# stepper_motor_control_sch.net
KiCad netlist of a schematic drawn in Altium Designer
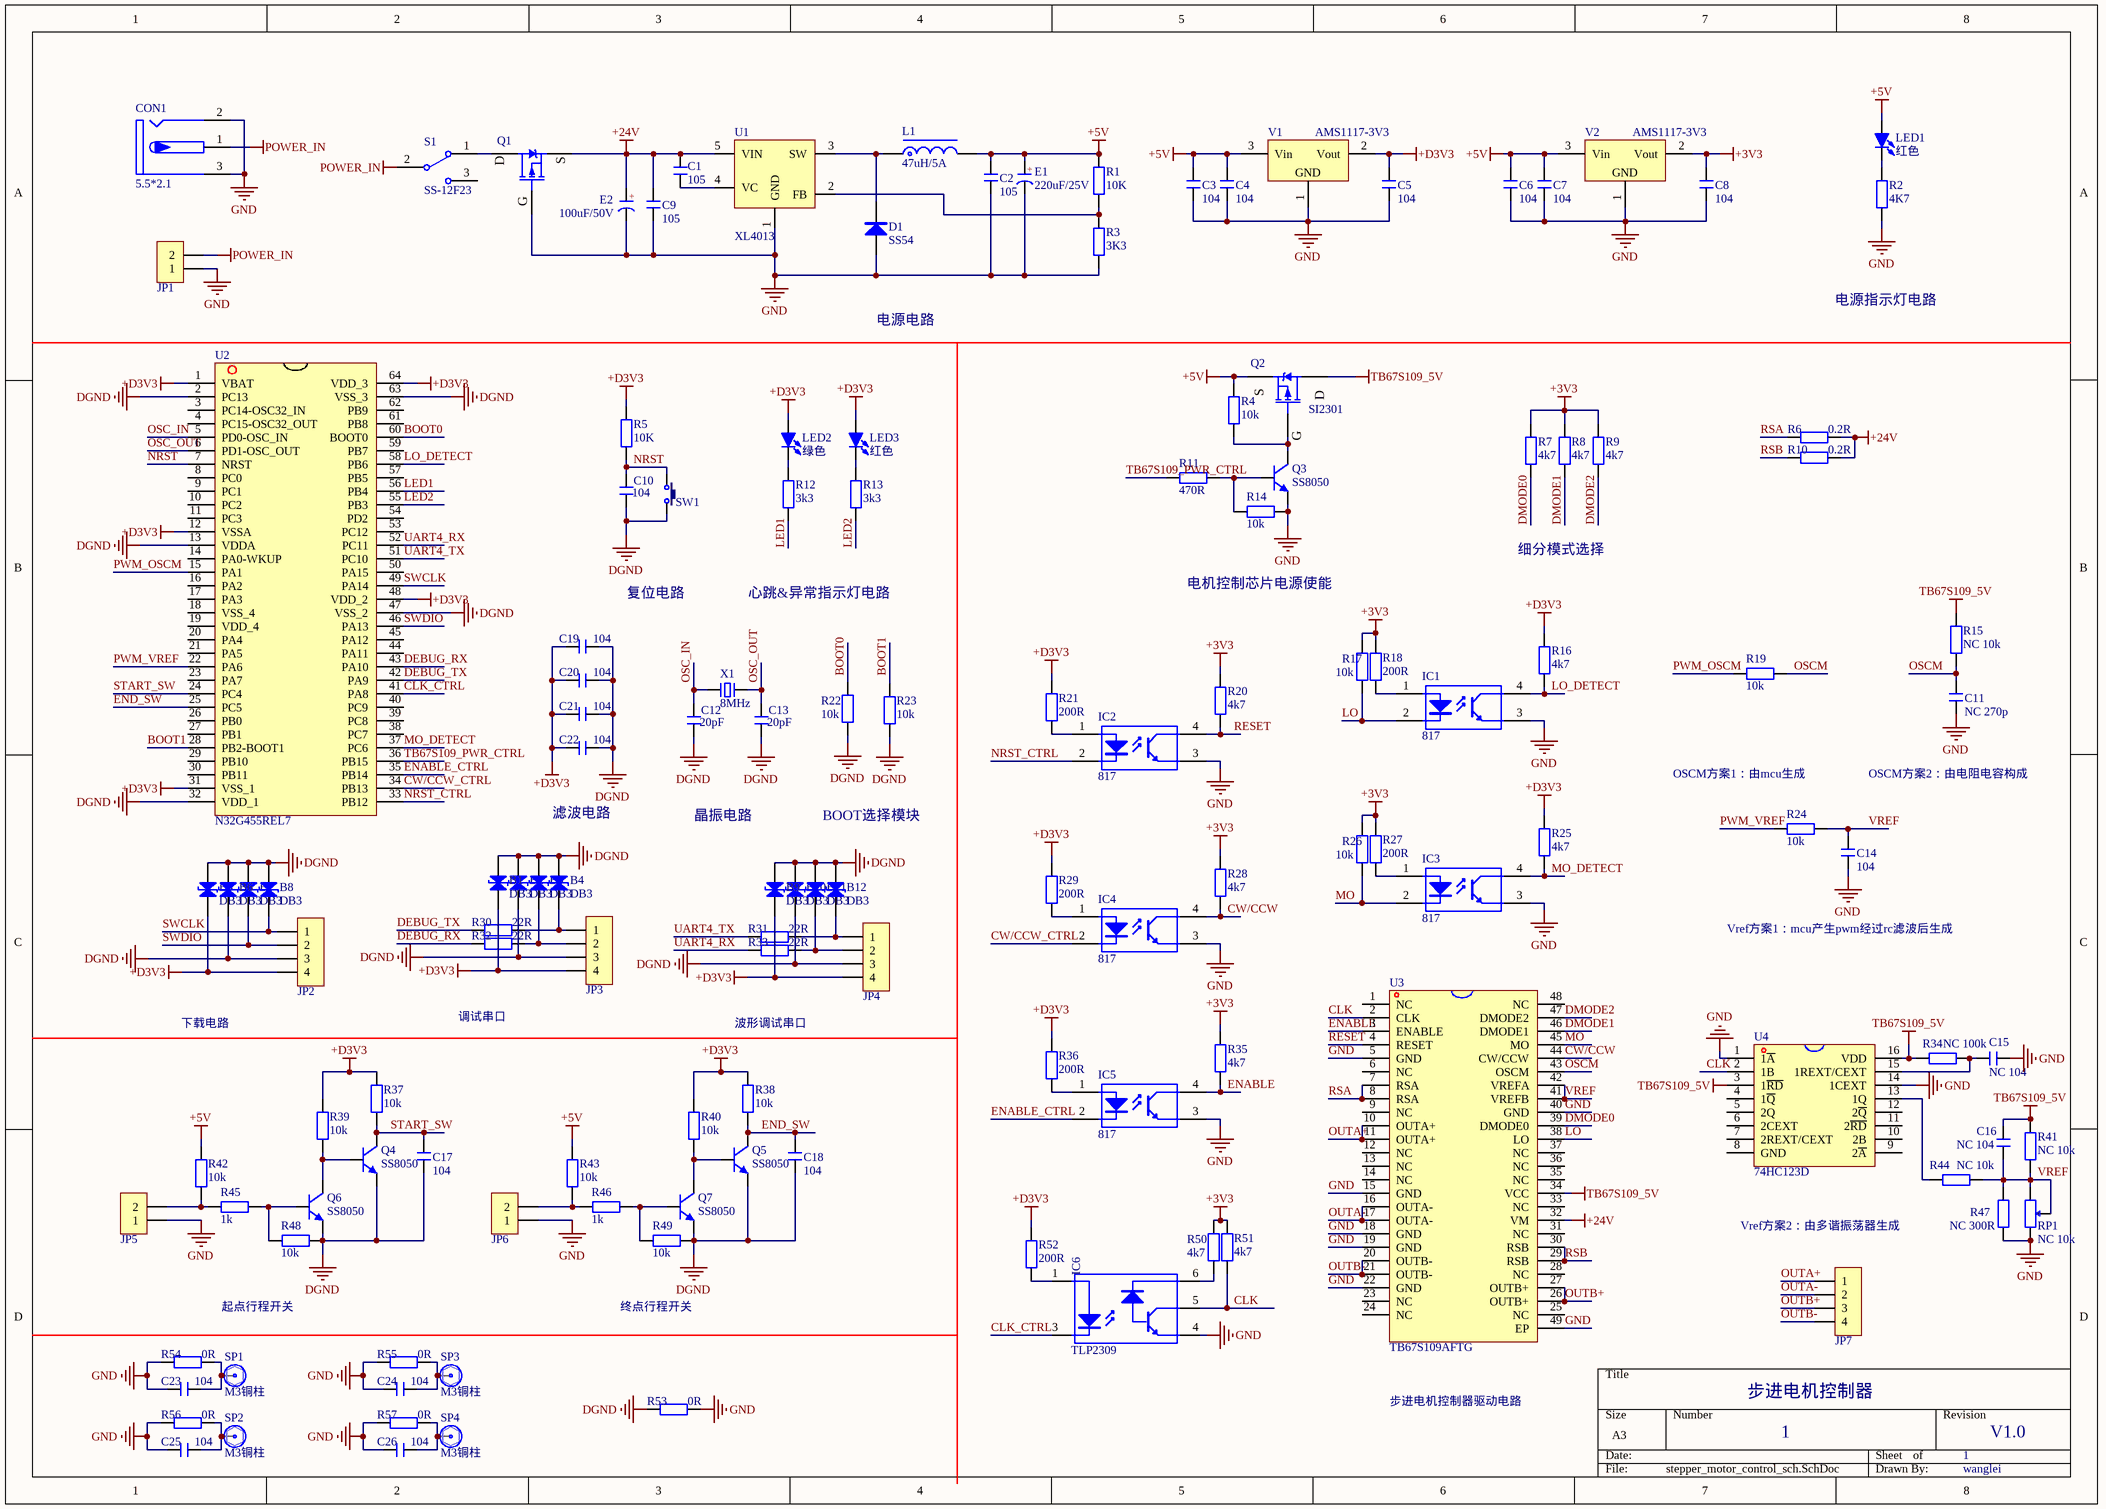
[diagram p0: stepper_motor_control_sch.SchDoc]

(export (version "E")
  (design (tool "Eeschema 10.0.6"))
  (components
    (comp (ref "B1")
      (value "DB3")
      (footprint "SOD-323")
      (description "双向触发二极管")
      (libsource (lib "8.1   - 二极管-整流桥") (part "DB3"))
    )
    (comp (ref "B2")
      (value "DB3")
      (footprint "SOD-323")
      (description "双向触发二极管")
      (libsource (lib "8.1   - 二极管-整流桥") (part "DB3"))
    )
    (comp (ref "B3")
      (value "DB3")
      (footprint "SOD-323")
      (description "双向触发二极管")
      (libsource (lib "8.1   - 二极管-整流桥") (part "DB3"))
    )
    (comp (ref "B4")
      (value "DB3")
      (footprint "SOD-323")
      (description "双向触发二极管")
      (libsource (lib "8.1   - 二极管-整流桥") (part "DB3"))
    )
    (comp (ref "B5")
      (value "DB3")
      (footprint "SOD-323")
      (description "双向触发二极管")
      (libsource (lib "8.1   - 二极管-整流桥") (part "DB3"))
    )
    (comp (ref "B6")
      (value "DB3")
      (footprint "SOD-323")
      (description "双向触发二极管")
      (libsource (lib "8.1   - 二极管-整流桥") (part "DB3"))
    )
    (comp (ref "B7")
      (value "DB3")
      (footprint "SOD-323")
      (description "双向触发二极管")
      (libsource (lib "8.1   - 二极管-整流桥") (part "DB3"))
    )
    (comp (ref "B8")
      (value "DB3")
      (footprint "SOD-323")
      (description "双向触发二极管")
      (libsource (lib "8.1   - 二极管-整流桥") (part "DB3"))
    )
    (comp (ref "B9")
      (value "DB3")
      (footprint "SOD-323")
      (description "双向触发二极管")
      (libsource (lib "8.1   - 二极管-整流桥") (part "DB3"))
    )
    (comp (ref "B10")
      (value "DB3")
      (footprint "SOD-323")
      (description "双向触发二极管")
      (libsource (lib "8.1   - 二极管-整流桥") (part "DB3"))
    )
    (comp (ref "B11")
      (value "DB3")
      (footprint "SOD-323")
      (description "双向触发二极管")
      (libsource (lib "8.1   - 二极管-整流桥") (part "DB3"))
    )
    (comp (ref "B12")
      (value "DB3")
      (footprint "SOD-323")
      (description "双向触发二极管")
      (libsource (lib "8.1   - 二极管-整流桥") (part "DB3"))
    )
    (comp (ref "C1")
      (value "105")
      (footprint "C 0603_M")
      (description "无极性贴片电容")
      (fields (field (name "版权归属") "源创客"))
      (libsource (lib "3.1   - 电阻-电容-电感") (part "C"))
    )
    (comp (ref "C2")
      (value "105")
      (footprint "C 0603_M")
      (description "无极性贴片电容")
      (fields (field (name "版权归属") "源创客"))
      (libsource (lib "3.1   - 电阻-电容-电感") (part "C"))
    )
    (comp (ref "C3")
      (value "104")
      (footprint "C 0603_M")
      (description "无极性贴片电容")
      (fields (field (name "版权归属") "源创客"))
      (libsource (lib "3.1   - 电阻-电容-电感") (part "C"))
    )
    (comp (ref "C4")
      (value "104")
      (footprint "C 0603_M")
      (description "无极性贴片电容")
      (fields (field (name "版权归属") "源创客"))
      (libsource (lib "3.1   - 电阻-电容-电感") (part "C"))
    )
    (comp (ref "C5")
      (value "104")
      (footprint "C 0603_M")
      (description "无极性贴片电容")
      (fields (field (name "版权归属") "源创客"))
      (libsource (lib "3.1   - 电阻-电容-电感") (part "C"))
    )
    (comp (ref "C6")
      (value "104")
      (footprint "C 0603_M")
      (description "无极性贴片电容")
      (fields (field (name "版权归属") "源创客"))
      (libsource (lib "3.1   - 电阻-电容-电感") (part "C"))
    )
    (comp (ref "C7")
      (value "104")
      (footprint "C 0603_M")
      (description "无极性贴片电容")
      (fields (field (name "版权归属") "源创客"))
      (libsource (lib "3.1   - 电阻-电容-电感") (part "C"))
    )
    (comp (ref "C8")
      (value "104")
      (footprint "C 0603_M")
      (description "无极性贴片电容")
      (fields (field (name "版权归属") "源创客"))
      (libsource (lib "3.1   - 电阻-电容-电感") (part "C"))
    )
    (comp (ref "C9")
      (value "105")
      (footprint "C 0603_M")
      (description "无极性贴片电容")
      (fields (field (name "版权归属") "源创客"))
      (libsource (lib "3.1   - 电阻-电容-电感") (part "C"))
    )
    (comp (ref "C10")
      (value "104")
      (footprint "C 0603_M")
      (description "无极性贴片电容")
      (fields (field (name "版权归属") "源创客"))
      (libsource (lib "3.1   - 电阻-电容-电感") (part "C"))
    )
    (comp (ref "C11")
      (value "NC 270p")
      (footprint "C 0603_M")
      (description "无极性贴片电容")
      (fields (field (name "版权归属") "源创客"))
      (libsource (lib "3.1   - 电阻-电容-电感") (part "C"))
    )
    (comp (ref "C12")
      (value "20pF")
      (footprint "C 0603_M")
      (description "无极性贴片电容")
      (fields (field (name "版权归属") "源创客"))
      (libsource (lib "3.1   - 电阻-电容-电感") (part "C"))
    )
    (comp (ref "C13")
      (value "20pF")
      (footprint "C 0603_M")
      (description "无极性贴片电容")
      (fields (field (name "版权归属") "源创客"))
      (libsource (lib "3.1   - 电阻-电容-电感") (part "C"))
    )
    (comp (ref "C14")
      (value "104")
      (footprint "C 0603_M")
      (description "无极性贴片电容")
      (fields (field (name "版权归属") "源创客"))
      (libsource (lib "3.1   - 电阻-电容-电感") (part "C"))
    )
    (comp (ref "C15")
      (value "NC 104")
      (footprint "C 0603_M")
      (description "无极性贴片电容")
      (fields (field (name "版权归属") "源创客"))
      (libsource (lib "3.1   - 电阻-电容-电感") (part "C"))
    )
    (comp (ref "C16")
      (value "NC 104")
      (footprint "C 0603_M")
      (description "无极性贴片电容")
      (fields (field (name "版权归属") "源创客"))
      (libsource (lib "3.1   - 电阻-电容-电感") (part "C"))
    )
    (comp (ref "C17")
      (value "104")
      (footprint "C 0603_M")
      (description "无极性贴片电容")
      (fields (field (name "版权归属") "源创客"))
      (libsource (lib "3.1   - 电阻-电容-电感") (part "C"))
    )
    (comp (ref "C18")
      (value "104")
      (footprint "C 0603_M")
      (description "无极性贴片电容")
      (fields (field (name "版权归属") "源创客"))
      (libsource (lib "3.1   - 电阻-电容-电感") (part "C"))
    )
    (comp (ref "C19")
      (value "104")
      (footprint "C 0603_M")
      (description "无极性贴片电容")
      (fields (field (name "版权归属") "源创客"))
      (libsource (lib "3.1   - 电阻-电容-电感") (part "C"))
    )
    (comp (ref "C20")
      (value "104")
      (footprint "C 0603_M")
      (description "无极性贴片电容")
      (fields (field (name "版权归属") "源创客"))
      (libsource (lib "3.1   - 电阻-电容-电感") (part "C"))
    )
    (comp (ref "C21")
      (value "104")
      (footprint "C 0603_M")
      (description "无极性贴片电容")
      (fields (field (name "版权归属") "源创客"))
      (libsource (lib "3.1   - 电阻-电容-电感") (part "C"))
    )
    (comp (ref "C22")
      (value "104")
      (footprint "C 0603_M")
      (description "无极性贴片电容")
      (fields (field (name "版权归属") "源创客"))
      (libsource (lib "3.1   - 电阻-电容-电感") (part "C"))
    )
    (comp (ref "C23")
      (value "104")
      (footprint "C 0603_M")
      (description "无极性贴片电容")
      (fields (field (name "版权归属") "源创客"))
      (libsource (lib "3.1   - 电阻-电容-电感") (part "C"))
    )
    (comp (ref "C24")
      (value "104")
      (footprint "C 0603_M")
      (description "无极性贴片电容")
      (fields (field (name "版权归属") "源创客"))
      (libsource (lib "3.1   - 电阻-电容-电感") (part "C"))
    )
    (comp (ref "C25")
      (value "104")
      (footprint "C 0603_M")
      (description "无极性贴片电容")
      (fields (field (name "版权归属") "源创客"))
      (libsource (lib "3.1   - 电阻-电容-电感") (part "C"))
    )
    (comp (ref "C26")
      (value "104")
      (footprint "C 0603_M")
      (description "无极性贴片电容")
      (fields (field (name "版权归属") "源创客"))
      (libsource (lib "3.1   - 电阻-电容-电感") (part "C"))
    )
    (comp (ref "CON1")
      (value "5.5*2.1")
      (footprint "DC-005")
      (description "带屏蔽DC电源接口")
      (fields (field (name "版权归属") "源创客"))
      (libsource (lib "4.1   - 接口类") (part "DC-005P"))
    )
    (comp (ref "D1")
      (value "SS54")
      (footprint "SMB")
      (description "肖特基二极管")
      (fields (field (name "版权归属") "源创客"))
      (libsource (lib "8.1   - 二极管-整流桥") (part "SS24"))
    )
    (comp (ref "E1")
      (value "220uF/25V")
      (footprint "CAP 2.5*6.3*11.2 - BK")
      (description "直插电解电容")
      (fields (field (name "版权归属") "源创客"))
      (libsource (lib "3.1   - 电阻-电容-电感") (part "C-CAP"))
    )
    (comp (ref "E2")
      (value "100uF/50V")
      (footprint "CAP 3.5*8*11.5 - BK")
      (description "直插电解电容")
      (fields (field (name "版权归属") "源创客"))
      (libsource (lib "3.1   - 电阻-电容-电感") (part "C-CAP"))
    )
    (comp (ref "IC1")
      (value "817")
      (footprint "SMD")
      (description "线性光耦")
      (fields (field (name "版权归属") "源创客"))
      (libsource (lib "11.1 - 传感元件") (part "817"))
    )
    (comp (ref "IC2")
      (value "817")
      (footprint "SMD")
      (description "线性光耦")
      (fields (field (name "版权归属") "源创客"))
      (libsource (lib "11.1 - 传感元件") (part "817"))
    )
    (comp (ref "IC3")
      (value "817")
      (footprint "SMD")
      (description "线性光耦")
      (fields (field (name "版权归属") "源创客"))
      (libsource (lib "11.1 - 传感元件") (part "817"))
    )
    (comp (ref "IC4")
      (value "817")
      (footprint "SMD")
      (description "线性光耦")
      (fields (field (name "版权归属") "源创客"))
      (libsource (lib "11.1 - 传感元件") (part "817"))
    )
    (comp (ref "IC5")
      (value "817")
      (footprint "SMD")
      (description "线性光耦")
      (fields (field (name "版权归属") "源创客"))
      (libsource (lib "11.1 - 传感元件") (part "817"))
    )
    (comp (ref "IC6")
      (value "TLP2309")
      (footprint "SO-6")
      (description "高速光耦")
      (libsource (lib "11.1 - 传感元件") (part "TLP2309"))
    )
    (comp (ref "JP1")
      (value "HDR-1X2")
      (footprint "KF350-2P")
      (description "2P接插件")
      (fields (field (name "版权归属") "源创客"))
      (libsource (lib "4.6   - 接插件-脚距3.5") (part "Header 2"))
    )
    (comp (ref "JP2")
      (value "HDR-1X4")
      (footprint "MX 1.25-WS-4P")
      (description "4P接插件")
      (fields (field (name "版权归属") "源创客"))
      (libsource (lib "4.2   - 接插件-脚距1.25") (part "Header 4"))
    )
    (comp (ref "JP3")
      (value "HDR-1X4")
      (footprint "MX 1.25-WS-4P")
      (description "4P接插件")
      (fields (field (name "版权归属") "源创客"))
      (libsource (lib "4.2   - 接插件-脚距1.25") (part "Header 4"))
    )
    (comp (ref "JP4")
      (value "HDR-1X4")
      (footprint "MX 1.25-WS-4P")
      (description "4P接插件")
      (fields (field (name "版权归属") "源创客"))
      (libsource (lib "4.2   - 接插件-脚距1.25") (part "Header 4"))
    )
    (comp (ref "JP5")
      (value "HDR-1X2")
      (footprint "XH2.54-LI-2P")
      (description "2P接插件")
      (fields (field (name "版权归属") "源创客"))
      (libsource (lib "4.5   - 接插件-脚距2.54") (part "Header 2"))
    )
    (comp (ref "JP6")
      (value "HDR-1X2")
      (footprint "XH2.54-LI-2P")
      (description "2P接插件")
      (fields (field (name "版权归属") "源创客"))
      (libsource (lib "4.5   - 接插件-脚距2.54") (part "Header 2"))
    )
    (comp (ref "JP7")
      (value "HDR-1X4")
      (footprint "KF350-4P")
      (description "4P接插件")
      (fields (field (name "版权归属") "源创客"))
      (libsource (lib "4.6   - 接插件-脚距3.5") (part "Header 4"))
    )
    (comp (ref "L1")
      (value "47uH/5A")
      (footprint "LMR135")
      (description "功率磁环电感")
      (fields (field (name "版权归属") "源创客"))
      (libsource (lib "3.1   - 电阻-电容-电感") (part "L-MR"))
    )
    (comp (ref "LED1")
      (value "红色")
      (footprint "LED 0805W")
      (description "贴片LED")
      (fields (field (name "版权归属") "源创客"))
      (libsource (lib "9.1   - LED") (part "LED-SMD"))
    )
    (comp (ref "LED2")
      (value "绿色")
      (footprint "LED 0805W")
      (description "贴片LED")
      (fields (field (name "版权归属") "源创客"))
      (libsource (lib "9.1   - LED") (part "LED-SMD"))
    )
    (comp (ref "LED3")
      (value "红色")
      (footprint "LED 0805W")
      (description "贴片LED")
      (fields (field (name "版权归属") "源创客"))
      (libsource (lib "9.1   - LED") (part "LED-SMD"))
    )
    (comp (ref "Q1")
      (value "D15P05")
      (footprint "TO252")
      (description "P沟道场效应管")
      (fields (field (name "版权归属") "源创客"))
      (libsource (lib "6.1   - 场效应管-可控硅") (part "D15P05"))
    )
    (comp (ref "Q2")
      (value "SI2301")
      (footprint "SOT23-3N")
      (description "P沟道场效应管")
      (fields (field (name "版权归属") "源创客"))
      (libsource (lib "6.1   - 场效应管-可控硅") (part "SI2301"))
    )
    (comp (ref "Q3")
      (value "SS8050")
      (footprint "SOT23-3N")
      (description "高频放大-NPN型")
      (fields (field (name "版权归属") "源创客"))
      (libsource (lib "6.2   - 三极管") (part "8050-SMD"))
    )
    (comp (ref "Q4")
      (value "SS8050")
      (footprint "SOT23-3N")
      (description "高频放大-NPN型")
      (fields (field (name "版权归属") "源创客"))
      (libsource (lib "6.2   - 三极管") (part "8050-SMD"))
    )
    (comp (ref "Q5")
      (value "SS8050")
      (footprint "SOT23-3N")
      (description "高频放大-NPN型")
      (fields (field (name "版权归属") "源创客"))
      (libsource (lib "6.2   - 三极管") (part "8050-SMD"))
    )
    (comp (ref "Q6")
      (value "SS8050")
      (footprint "SOT23-3N")
      (description "高频放大-NPN型")
      (fields (field (name "版权归属") "源创客"))
      (libsource (lib "6.2   - 三极管") (part "8050-SMD"))
    )
    (comp (ref "Q7")
      (value "SS8050")
      (footprint "SOT23-3N")
      (description "高频放大-NPN型")
      (fields (field (name "版权归属") "源创客"))
      (libsource (lib "6.2   - 三极管") (part "8050-SMD"))
    )
    (comp (ref "R1")
      (value "10K")
      (footprint "R 0603_M")
      (description "贴片电阻")
      (fields (field (name "版权归属") "源创客"))
      (libsource (lib "3.1   - 电阻-电容-电感") (part "R"))
    )
    (comp (ref "R2")
      (value "4K7")
      (footprint "R 0603_M")
      (description "贴片电阻")
      (fields (field (name "版权归属") "源创客"))
      (libsource (lib "3.1   - 电阻-电容-电感") (part "R"))
    )
    (comp (ref "R3")
      (value "3K3")
      (footprint "R 0603_M")
      (description "贴片电阻")
      (fields (field (name "版权归属") "源创客"))
      (libsource (lib "3.1   - 电阻-电容-电感") (part "R"))
    )
    (comp (ref "R4")
      (value "10k")
      (footprint "R 0603_M")
      (description "贴片电阻")
      (fields (field (name "版权归属") "源创客"))
      (libsource (lib "3.1   - 电阻-电容-电感") (part "R"))
    )
    (comp (ref "R5")
      (value "10K")
      (footprint "R 0603_M")
      (description "贴片电阻")
      (fields (field (name "版权归属") "源创客"))
      (libsource (lib "3.1   - 电阻-电容-电感") (part "R"))
    )
    (comp (ref "R6")
      (value "0.2R")
      (footprint "R 2010_M")
      (description "贴片电阻")
      (fields (field (name "版权归属") "源创客"))
      (libsource (lib "3.1   - 电阻-电容-电感") (part "R"))
    )
    (comp (ref "R7")
      (value "4k7")
      (footprint "R 0603_M")
      (description "贴片电阻")
      (fields (field (name "版权归属") "源创客"))
      (libsource (lib "3.1   - 电阻-电容-电感") (part "R"))
    )
    (comp (ref "R8")
      (value "4k7")
      (footprint "R 0603_M")
      (description "贴片电阻")
      (fields (field (name "版权归属") "源创客"))
      (libsource (lib "3.1   - 电阻-电容-电感") (part "R"))
    )
    (comp (ref "R9")
      (value "4k7")
      (footprint "R 0603_M")
      (description "贴片电阻")
      (fields (field (name "版权归属") "源创客"))
      (libsource (lib "3.1   - 电阻-电容-电感") (part "R"))
    )
    (comp (ref "R10")
      (value "0.2R")
      (footprint "R 2010_M")
      (description "贴片电阻")
      (fields (field (name "版权归属") "源创客"))
      (libsource (lib "3.1   - 电阻-电容-电感") (part "R"))
    )
    (comp (ref "R11")
      (value "470R")
      (footprint "R 0603_M")
      (description "贴片电阻")
      (fields (field (name "版权归属") "源创客"))
      (libsource (lib "3.1   - 电阻-电容-电感") (part "R"))
    )
    (comp (ref "R12")
      (value "3k3")
      (footprint "R 0603_M")
      (description "贴片电阻")
      (fields (field (name "版权归属") "源创客"))
      (libsource (lib "3.1   - 电阻-电容-电感") (part "R"))
    )
    (comp (ref "R13")
      (value "3k3")
      (footprint "R 0603_M")
      (description "贴片电阻")
      (fields (field (name "版权归属") "源创客"))
      (libsource (lib "3.1   - 电阻-电容-电感") (part "R"))
    )
    (comp (ref "R14")
      (value "10k")
      (footprint "R 0603_M")
      (description "贴片电阻")
      (fields (field (name "版权归属") "源创客"))
      (libsource (lib "3.1   - 电阻-电容-电感") (part "R"))
    )
    (comp (ref "R15")
      (value "NC 10k")
      (footprint "R 0603_M")
      (description "贴片电阻")
      (fields (field (name "版权归属") "源创客"))
      (libsource (lib "3.1   - 电阻-电容-电感") (part "R"))
    )
    (comp (ref "R16")
      (value "4k7")
      (footprint "R 0603_M")
      (description "贴片电阻")
      (fields (field (name "版权归属") "源创客"))
      (libsource (lib "3.1   - 电阻-电容-电感") (part "R"))
    )
    (comp (ref "R17")
      (value "10k")
      (footprint "R 0603_M")
      (description "贴片电阻")
      (fields (field (name "版权归属") "源创客"))
      (libsource (lib "3.1   - 电阻-电容-电感") (part "R"))
    )
    (comp (ref "R18")
      (value "200R")
      (footprint "R 0603_M")
      (description "贴片电阻")
      (fields (field (name "版权归属") "源创客"))
      (libsource (lib "3.1   - 电阻-电容-电感") (part "R"))
    )
    (comp (ref "R19")
      (value "10k")
      (footprint "R 0603_M")
      (description "贴片电阻")
      (fields (field (name "版权归属") "源创客"))
      (libsource (lib "3.1   - 电阻-电容-电感") (part "R"))
    )
    (comp (ref "R20")
      (value "4k7")
      (footprint "R 0603_M")
      (description "贴片电阻")
      (fields (field (name "版权归属") "源创客"))
      (libsource (lib "3.1   - 电阻-电容-电感") (part "R"))
    )
    (comp (ref "R21")
      (value "200R")
      (footprint "R 0603_M")
      (description "贴片电阻")
      (fields (field (name "版权归属") "源创客"))
      (libsource (lib "3.1   - 电阻-电容-电感") (part "R"))
    )
    (comp (ref "R22")
      (value "10k")
      (footprint "R 0603_M")
      (description "贴片电阻")
      (fields (field (name "版权归属") "源创客"))
      (libsource (lib "3.1   - 电阻-电容-电感") (part "R"))
    )
    (comp (ref "R23")
      (value "10k")
      (footprint "R 0603_M")
      (description "贴片电阻")
      (fields (field (name "版权归属") "源创客"))
      (libsource (lib "3.1   - 电阻-电容-电感") (part "R"))
    )
    (comp (ref "R24")
      (value "10k")
      (footprint "R 0603_M")
      (description "贴片电阻")
      (fields (field (name "版权归属") "源创客"))
      (libsource (lib "3.1   - 电阻-电容-电感") (part "R"))
    )
    (comp (ref "R25")
      (value "4k7")
      (footprint "R 0603_M")
      (description "贴片电阻")
      (fields (field (name "版权归属") "源创客"))
      (libsource (lib "3.1   - 电阻-电容-电感") (part "R"))
    )
    (comp (ref "R26")
      (value "10k")
      (footprint "R 0603_M")
      (description "贴片电阻")
      (fields (field (name "版权归属") "源创客"))
      (libsource (lib "3.1   - 电阻-电容-电感") (part "R"))
    )
    (comp (ref "R27")
      (value "200R")
      (footprint "R 0603_M")
      (description "贴片电阻")
      (fields (field (name "版权归属") "源创客"))
      (libsource (lib "3.1   - 电阻-电容-电感") (part "R"))
    )
    (comp (ref "R28")
      (value "4k7")
      (footprint "R 0603_M")
      (description "贴片电阻")
      (fields (field (name "版权归属") "源创客"))
      (libsource (lib "3.1   - 电阻-电容-电感") (part "R"))
    )
    (comp (ref "R29")
      (value "200R")
      (footprint "R 0603_M")
      (description "贴片电阻")
      (fields (field (name "版权归属") "源创客"))
      (libsource (lib "3.1   - 电阻-电容-电感") (part "R"))
    )
    (comp (ref "R30")
      (value "22R")
      (footprint "R 0603_M")
      (description "贴片电阻")
      (fields (field (name "版权归属") "源创客"))
      (libsource (lib "3.1   - 电阻-电容-电感") (part "R"))
    )
    (comp (ref "R31")
      (value "22R")
      (footprint "R 0603_M")
      (description "贴片电阻")
      (fields (field (name "版权归属") "源创客"))
      (libsource (lib "3.1   - 电阻-电容-电感") (part "R"))
    )
    (comp (ref "R32")
      (value "22R")
      (footprint "R 0603_M")
      (description "贴片电阻")
      (fields (field (name "版权归属") "源创客"))
      (libsource (lib "3.1   - 电阻-电容-电感") (part "R"))
    )
    (comp (ref "R33")
      (value "22R")
      (footprint "R 0603_M")
      (description "贴片电阻")
      (fields (field (name "版权归属") "源创客"))
      (libsource (lib "3.1   - 电阻-电容-电感") (part "R"))
    )
    (comp (ref "R34")
      (value "NC 100k")
      (footprint "R 0603_M")
      (description "贴片电阻")
      (fields (field (name "版权归属") "源创客"))
      (libsource (lib "3.1   - 电阻-电容-电感") (part "R"))
    )
    (comp (ref "R35")
      (value "4k7")
      (footprint "R 0603_M")
      (description "贴片电阻")
      (fields (field (name "版权归属") "源创客"))
      (libsource (lib "3.1   - 电阻-电容-电感") (part "R"))
    )
    (comp (ref "R36")
      (value "200R")
      (footprint "R 0603_M")
      (description "贴片电阻")
      (fields (field (name "版权归属") "源创客"))
      (libsource (lib "3.1   - 电阻-电容-电感") (part "R"))
    )
    (comp (ref "R37")
      (value "10k")
      (footprint "R 0603_M")
      (description "贴片电阻")
      (fields (field (name "版权归属") "源创客"))
      (libsource (lib "3.1   - 电阻-电容-电感") (part "R"))
    )
    (comp (ref "R38")
      (value "10k")
      (footprint "R 0603_M")
      (description "贴片电阻")
      (fields (field (name "版权归属") "源创客"))
      (libsource (lib "3.1   - 电阻-电容-电感") (part "R"))
    )
    (comp (ref "R39")
      (value "10k")
      (footprint "R 0603_M")
      (description "贴片电阻")
      (fields (field (name "版权归属") "源创客"))
      (libsource (lib "3.1   - 电阻-电容-电感") (part "R"))
    )
    (comp (ref "R40")
      (value "10k")
      (footprint "R 0603_M")
      (description "贴片电阻")
      (fields (field (name "版权归属") "源创客"))
      (libsource (lib "3.1   - 电阻-电容-电感") (part "R"))
    )
    (comp (ref "R41")
      (value "NC 10k")
      (footprint "R 0603_M")
      (description "贴片电阻")
      (fields (field (name "版权归属") "源创客"))
      (libsource (lib "3.1   - 电阻-电容-电感") (part "R"))
    )
    (comp (ref "R42")
      (value "10k")
      (footprint "R 0603_M")
      (description "贴片电阻")
      (fields (field (name "版权归属") "源创客"))
      (libsource (lib "3.1   - 电阻-电容-电感") (part "R"))
    )
    (comp (ref "R43")
      (value "10k")
      (footprint "R 0603_M")
      (description "贴片电阻")
      (fields (field (name "版权归属") "源创客"))
      (libsource (lib "3.1   - 电阻-电容-电感") (part "R"))
    )
    (comp (ref "R44")
      (value "NC 10k")
      (footprint "R 0603_M")
      (description "贴片电阻")
      (fields (field (name "版权归属") "源创客"))
      (libsource (lib "3.1   - 电阻-电容-电感") (part "R"))
    )
    (comp (ref "R45")
      (value "1k")
      (footprint "R 0603_M")
      (description "贴片电阻")
      (fields (field (name "版权归属") "源创客"))
      (libsource (lib "3.1   - 电阻-电容-电感") (part "R"))
    )
    (comp (ref "R46")
      (value "1k")
      (footprint "R 0603_M")
      (description "贴片电阻")
      (fields (field (name "版权归属") "源创客"))
      (libsource (lib "3.1   - 电阻-电容-电感") (part "R"))
    )
    (comp (ref "R47")
      (value "NC 300R")
      (footprint "R 0603_M")
      (description "贴片电阻")
      (fields (field (name "版权归属") "源创客"))
      (libsource (lib "3.1   - 电阻-电容-电感") (part "R"))
    )
    (comp (ref "R48")
      (value "10k")
      (footprint "R 0603_M")
      (description "贴片电阻")
      (fields (field (name "版权归属") "源创客"))
      (libsource (lib "3.1   - 电阻-电容-电感") (part "R"))
    )
    (comp (ref "R49")
      (value "10k")
      (footprint "R 0603_M")
      (description "贴片电阻")
      (fields (field (name "版权归属") "源创客"))
      (libsource (lib "3.1   - 电阻-电容-电感") (part "R"))
    )
    (comp (ref "R50")
      (value "4k7")
      (footprint "R 0603_M")
      (description "贴片电阻")
      (fields (field (name "版权归属") "源创客"))
      (libsource (lib "3.1   - 电阻-电容-电感") (part "R"))
    )
    (comp (ref "R51")
      (value "4k7")
      (footprint "R 0603_M")
      (description "贴片电阻")
      (fields (field (name "版权归属") "源创客"))
      (libsource (lib "3.1   - 电阻-电容-电感") (part "R"))
    )
    (comp (ref "R52")
      (value "200R")
      (footprint "R 0603_M")
      (description "贴片电阻")
      (fields (field (name "版权归属") "源创客"))
      (libsource (lib "3.1   - 电阻-电容-电感") (part "R"))
    )
    (comp (ref "R53")
      (value "0R")
      (footprint "R 0603_M")
      (description "贴片电阻")
      (fields (field (name "版权归属") "源创客"))
      (libsource (lib "3.1   - 电阻-电容-电感") (part "R"))
    )
    (comp (ref "R54")
      (value "0R")
      (footprint "R 0603_M")
      (description "贴片电阻")
      (fields (field (name "版权归属") "源创客"))
      (libsource (lib "3.1   - 电阻-电容-电感") (part "R"))
    )
    (comp (ref "R55")
      (value "0R")
      (footprint "R 0603_M")
      (description "贴片电阻")
      (fields (field (name "版权归属") "源创客"))
      (libsource (lib "3.1   - 电阻-电容-电感") (part "R"))
    )
    (comp (ref "R56")
      (value "0R")
      (footprint "R 0603_M")
      (description "贴片电阻")
      (fields (field (name "版权归属") "源创客"))
      (libsource (lib "3.1   - 电阻-电容-电感") (part "R"))
    )
    (comp (ref "R57")
      (value "0R")
      (footprint "R 0603_M")
      (description "贴片电阻")
      (fields (field (name "版权归属") "源创客"))
      (libsource (lib "3.1   - 电阻-电容-电感") (part "R"))
    )
    (comp (ref "RP1")
      (value "NC 10k")
      (footprint "3303W")
      (description "贴片电位器")
      (fields (field (name "版权归属") "源创客"))
      (libsource (lib "3.1   - 电阻-电容-电感") (part "RP-SMD"))
    )
    (comp (ref "S1")
      (value "SS-12F23")
      (footprint "SK12D07VG3")
      (description "1路波动开关")
      (fields (field (name "版权归属") "源创客"))
      (libsource (lib "5.1   - 按键-开关") (part "SSW-1P"))
    )
    (comp (ref "SP1")
      (value "M3铜柱")
      (footprint "M3x4+6_N")
      (description "铜柱")
      (fields (field (name "版权归属") "源创客"))
      (libsource (lib "15.1 - 未分类器件") (part "铜柱加头大焊盘"))
    )
    (comp (ref "SP2")
      (value "M3铜柱")
      (footprint "M3x4+6_N")
      (description "铜柱")
      (fields (field (name "版权归属") "源创客"))
      (libsource (lib "15.1 - 未分类器件") (part "铜柱加头大焊盘"))
    )
    (comp (ref "SP3")
      (value "M3铜柱")
      (footprint "M3x4+6_N")
      (description "铜柱")
      (fields (field (name "版权归属") "源创客"))
      (libsource (lib "15.1 - 未分类器件") (part "铜柱加头大焊盘"))
    )
    (comp (ref "SP4")
      (value "M3铜柱")
      (footprint "M3x4+6_N")
      (description "铜柱")
      (fields (field (name "版权归属") "源创客"))
      (libsource (lib "15.1 - 未分类器件") (part "铜柱加头大焊盘"))
    )
    (comp (ref "SW1")
      (value "3x6x5")
      (footprint "TSW SMD-3*6*2.5")
      (description "3x6轻触开关")
      (fields (field (name "版权归属") "源创客"))
      (libsource (lib "5.1   - 按键-开关") (part "TSW 3x6"))
    )
    (comp (ref "U1")
      (value "XL4013")
      (footprint "TO252-5")
      (description "DC-DC降压芯片 最大4A输出")
      (libsource (lib "1.3   - 电源类芯片") (part "XL4013"))
    )
    (comp (ref "U2")
      (value "N32G455REL7")
      (footprint "LQFP64 10x10_M")
      (description "国民技术32位mcu IO:64")
      (libsource (lib "2.1   - STM32系列单片机") (part "N32G455REL7"))
    )
    (comp (ref "U3")
      (value "TB67S109AFTG")
      (footprint "QFN48")
      (description "时钟控制双极性步进电机驱动器")
      (libsource (lib "16.1 - 驱动IC") (part "TB67S109AFTG"))
    )
    (comp (ref "U4")
      (value "74HC123D")
      (footprint "SOP16_L")
      (description "单稳态多谐振荡器")
      (libsource (lib "1.2   - 74系列芯片") (part "74HC123D"))
    )
    (comp (ref "V1")
      (value "AMS1117-3V3")
      (footprint "SOT223_M")
      (description "三端稳压芯片")
      (fields (field (name "版权归属") "源创客"))
      (libsource (lib "1.3   - 电源类芯片") (part "AMS1117"))
    )
    (comp (ref "V2")
      (value "AMS1117-3V3")
      (footprint "SOT223_M")
      (description "三端稳压芯片")
      (fields (field (name "版权归属") "源创客"))
      (libsource (lib "1.3   - 电源类芯片") (part "AMS1117"))
    )
    (comp (ref "X1")
      (value "8MHz")
      (footprint "OSC HC-49SMD")
      (description "2脚无源脚晶振")
      (fields (field (name "版权归属") "源创客"))
      (libsource (lib "10.1 - 保险丝-晶振") (part "XTAL-2P"))
    )
  )
  (nets
    (net (code "1") (name "+3V3") (class "Default")
      (node (ref "C8") (pin "1") (pinfunction "1_1") (pintype "passive"))
      (node (ref "R17") (pin "1") (pinfunction "1_1") (pintype "passive"))
      (node (ref "R18") (pin "1") (pinfunction "1_1") (pintype "passive"))
      (node (ref "R20") (pin "2") (pinfunction "2_2") (pintype "passive"))
      (node (ref "R26") (pin "1") (pinfunction "1_1") (pintype "passive"))
      (node (ref "R27") (pin "1") (pinfunction "1_1") (pintype "passive"))
      (node (ref "R28") (pin "2") (pinfunction "2_2") (pintype "passive"))
      (node (ref "R35") (pin "2") (pinfunction "2_2") (pintype "passive"))
      (node (ref "R50") (pin "1") (pinfunction "1_1") (pintype "passive"))
      (node (ref "R51") (pin "1") (pinfunction "1_1") (pintype "passive"))
      (node (ref "R7") (pin "2") (pinfunction "2_2") (pintype "passive"))
      (node (ref "R8") (pin "2") (pinfunction "2_2") (pintype "passive"))
      (node (ref "R9") (pin "2") (pinfunction "2_2") (pintype "passive"))
      (node (ref "V2") (pin "2") (pinfunction "Vout_2") (pintype "passive"))
    )
    (net (code "2") (name "+5V") (class "Default")
      (node (ref "C2") (pin "1") (pinfunction "1_1") (pintype "passive"))
      (node (ref "C3") (pin "1") (pinfunction "1_1") (pintype "passive"))
      (node (ref "C4") (pin "1") (pinfunction "1_1") (pintype "passive"))
      (node (ref "C6") (pin "1") (pinfunction "1_1") (pintype "passive"))
      (node (ref "C7") (pin "1") (pinfunction "1_1") (pintype "passive"))
      (node (ref "E1") (pin "1") (pinfunction "A_1") (pintype "passive"))
      (node (ref "L1") (pin "2") (pinfunction "2_2") (pintype "passive"))
      (node (ref "LED1") (pin "1") (pinfunction "A_1") (pintype "passive"))
      (node (ref "Q2") (pin "2") (pinfunction "S_2") (pintype "passive"))
      (node (ref "R1") (pin "2") (pinfunction "2_2") (pintype "passive"))
      (node (ref "R4") (pin "2") (pinfunction "2_2") (pintype "passive"))
      (node (ref "R42") (pin "2") (pinfunction "2_2") (pintype "passive"))
      (node (ref "R43") (pin "2") (pinfunction "2_2") (pintype "passive"))
      (node (ref "V1") (pin "3") (pinfunction "Vin_3") (pintype "passive"))
      (node (ref "V2") (pin "3") (pinfunction "Vin_3") (pintype "passive"))
    )
    (net (code "3") (name "+24V") (class "Default")
      (node (ref "C1") (pin "1") (pinfunction "1_1") (pintype "passive"))
      (node (ref "C9") (pin "1") (pinfunction "1_1") (pintype "passive"))
      (node (ref "E2") (pin "1") (pinfunction "A_1") (pintype "passive"))
      (node (ref "Q1") (pin "3") (pinfunction "S_3") (pintype "passive"))
      (node (ref "R10") (pin "2") (pinfunction "2_2") (pintype "passive"))
      (node (ref "R6") (pin "2") (pinfunction "2_2") (pintype "passive"))
      (node (ref "U1") (pin "5") (pinfunction "VIN_5") (pintype "passive"))
      (node (ref "U3") (pin "32") (pinfunction "VM_32") (pintype "passive"))
    )
    (net (code "4") (name "+D3V3") (class "Default")
      (node (ref "B1") (pin "2") (pinfunction "K_2") (pintype "passive"))
      (node (ref "B5") (pin "2") (pinfunction "K_2") (pintype "passive"))
      (node (ref "B9") (pin "2") (pinfunction "K_2") (pintype "passive"))
      (node (ref "C19") (pin "2") (pinfunction "2_2") (pintype "passive"))
      (node (ref "C20") (pin "2") (pinfunction "2_2") (pintype "passive"))
      (node (ref "C21") (pin "2") (pinfunction "2_2") (pintype "passive"))
      (node (ref "C22") (pin "2") (pinfunction "2_2") (pintype "passive"))
      (node (ref "C5") (pin "1") (pinfunction "1_1") (pintype "passive"))
      (node (ref "JP2") (pin "4") (pinfunction "4_4") (pintype "passive"))
      (node (ref "JP3") (pin "4") (pinfunction "4_4") (pintype "passive"))
      (node (ref "JP4") (pin "4") (pinfunction "4_4") (pintype "passive"))
      (node (ref "LED2") (pin "1") (pinfunction "A_1") (pintype "passive"))
      (node (ref "LED3") (pin "1") (pinfunction "A_1") (pintype "passive"))
      (node (ref "R16") (pin "2") (pinfunction "2_2") (pintype "passive"))
      (node (ref "R21") (pin "1") (pinfunction "1_1") (pintype "passive"))
      (node (ref "R25") (pin "2") (pinfunction "2_2") (pintype "passive"))
      (node (ref "R29") (pin "1") (pinfunction "1_1") (pintype "passive"))
      (node (ref "R36") (pin "1") (pinfunction "1_1") (pintype "passive"))
      (node (ref "R37") (pin "1") (pinfunction "1_1") (pintype "passive"))
      (node (ref "R38") (pin "1") (pinfunction "1_1") (pintype "passive"))
      (node (ref "R39") (pin "1") (pinfunction "1_1") (pintype "passive"))
      (node (ref "R40") (pin "1") (pinfunction "1_1") (pintype "passive"))
      (node (ref "R5") (pin "2") (pinfunction "2_2") (pintype "passive"))
      (node (ref "R52") (pin "1") (pinfunction "1_1") (pintype "passive"))
      (node (ref "U2") (pin "1") (pinfunction "VBAT_1") (pintype "passive"))
      (node (ref "U2") (pin "12") (pinfunction "VSSA_12") (pintype "passive"))
      (node (ref "U2") (pin "31") (pinfunction "VSS_1_31") (pintype "passive"))
      (node (ref "U2") (pin "48") (pinfunction "VDD_2_48") (pintype "passive"))
      (node (ref "U2") (pin "64") (pinfunction "VDD_3_64") (pintype "passive"))
      (node (ref "V1") (pin "2") (pinfunction "Vout_2") (pintype "passive"))
    )
    (net (code "5") (name "/BOOT0") (class "Default")
      (node (ref "R22") (pin "2") (pinfunction "2_2") (pintype "passive"))
      (node (ref "U2") (pin "60") (pinfunction "BOOT0_60") (pintype "passive"))
    )
    (net (code "6") (name "/BOOT1") (class "Default")
      (node (ref "R23") (pin "2") (pinfunction "2_2") (pintype "passive"))
      (node (ref "U2") (pin "28") (pinfunction "PB2-BOOT1_28") (pintype "passive"))
    )
    (net (code "7") (name "/CLK") (class "Default")
      (node (ref "IC6") (pin "5") (pinfunction "VO_5") (pintype "passive"))
      (node (ref "R51") (pin "2") (pinfunction "2_2") (pintype "passive"))
      (node (ref "U3") (pin "2") (pinfunction "CLK_2") (pintype "passive"))
      (node (ref "U4") (pin "2") (pinfunction "1B_2") (pintype "passive"))
    )
    (net (code "8") (name "/CLK_CTRL") (class "Default")
      (node (ref "IC6") (pin "3") (pinfunction "CA_3") (pintype "passive"))
      (node (ref "U2") (pin "41") (pinfunction "PA8_41") (pintype "passive"))
    )
    (net (code "9") (name "/CW{slash}CCW") (class "Default")
      (node (ref "IC4") (pin "4") (pinfunction "C_4") (pintype "passive"))
      (node (ref "R28") (pin "1") (pinfunction "1_1") (pintype "passive"))
      (node (ref "U3") (pin "44") (pinfunction "CW/CCW_44") (pintype "passive"))
    )
    (net (code "10") (name "/CW{slash}CCW_CTRL") (class "Default")
      (node (ref "IC4") (pin "2") (pinfunction "K_2") (pintype "passive"))
      (node (ref "U2") (pin "34") (pinfunction "PB13_34") (pintype "passive"))
    )
    (net (code "11") (name "/DEBUG_RX") (class "Default")
      (node (ref "R32") (pin "1") (pinfunction "1_1") (pintype "passive"))
      (node (ref "U2") (pin "43") (pinfunction "PA10_43") (pintype "passive"))
    )
    (net (code "12") (name "/DEBUG_TX") (class "Default")
      (node (ref "R30") (pin "1") (pinfunction "1_1") (pintype "passive"))
      (node (ref "U2") (pin "42") (pinfunction "PA9_42") (pintype "passive"))
    )
    (net (code "13") (name "/DMODE0") (class "Default")
      (node (ref "R7") (pin "1") (pinfunction "1_1") (pintype "passive"))
      (node (ref "U3") (pin "39") (pinfunction "DMODE0_39") (pintype "passive"))
    )
    (net (code "14") (name "/DMODE1") (class "Default")
      (node (ref "R8") (pin "1") (pinfunction "1_1") (pintype "passive"))
      (node (ref "U3") (pin "46") (pinfunction "DMODE1_46") (pintype "passive"))
    )
    (net (code "15") (name "/DMODE2") (class "Default")
      (node (ref "R9") (pin "1") (pinfunction "1_1") (pintype "passive"))
      (node (ref "U3") (pin "47") (pinfunction "DMODE2_47") (pintype "passive"))
    )
    (net (code "16") (name "/ENABLE") (class "Default")
      (node (ref "IC5") (pin "4") (pinfunction "C_4") (pintype "passive"))
      (node (ref "R35") (pin "1") (pinfunction "1_1") (pintype "passive"))
      (node (ref "U3") (pin "3") (pinfunction "ENABLE_3") (pintype "passive"))
    )
    (net (code "17") (name "/ENABLE_CTRL") (class "Default")
      (node (ref "IC5") (pin "2") (pinfunction "K_2") (pintype "passive"))
      (node (ref "U2") (pin "35") (pinfunction "PB14_35") (pintype "passive"))
    )
    (net (code "18") (name "/END_SW") (class "Default")
      (node (ref "C18") (pin "1") (pinfunction "1_1") (pintype "passive"))
      (node (ref "Q5") (pin "3") (pinfunction "C_3") (pintype "passive"))
      (node (ref "R38") (pin "2") (pinfunction "2_2") (pintype "passive"))
      (node (ref "U2") (pin "25") (pinfunction "PC5_25") (pintype "passive"))
    )
    (net (code "19") (name "/LED1") (class "Default")
      (node (ref "R12") (pin "1") (pinfunction "1_1") (pintype "passive"))
      (node (ref "U2") (pin "56") (pinfunction "PB4_56") (pintype "passive"))
    )
    (net (code "20") (name "/LED2") (class "Default")
      (node (ref "R13") (pin "1") (pinfunction "1_1") (pintype "passive"))
      (node (ref "U2") (pin "55") (pinfunction "PB3_55") (pintype "passive"))
    )
    (net (code "21") (name "/LO") (class "Default")
      (node (ref "IC1") (pin "2") (pinfunction "K_2") (pintype "passive"))
      (node (ref "R17") (pin "2") (pinfunction "2_2") (pintype "passive"))
      (node (ref "U3") (pin "38") (pinfunction "LO_38") (pintype "passive"))
    )
    (net (code "22") (name "/LO_DETECT") (class "Default")
      (node (ref "IC1") (pin "4") (pinfunction "C_4") (pintype "passive"))
      (node (ref "R16") (pin "1") (pinfunction "1_1") (pintype "passive"))
      (node (ref "U2") (pin "58") (pinfunction "PB6_58") (pintype "passive"))
    )
    (net (code "23") (name "/MO") (class "Default")
      (node (ref "IC3") (pin "2") (pinfunction "K_2") (pintype "passive"))
      (node (ref "R26") (pin "2") (pinfunction "2_2") (pintype "passive"))
      (node (ref "U3") (pin "45") (pinfunction "MO_45") (pintype "passive"))
    )
    (net (code "24") (name "/MO_DETECT") (class "Default")
      (node (ref "IC3") (pin "4") (pinfunction "C_4") (pintype "passive"))
      (node (ref "R25") (pin "1") (pinfunction "1_1") (pintype "passive"))
      (node (ref "U2") (pin "37") (pinfunction "PC6_37") (pintype "passive"))
    )
    (net (code "25") (name "/NRST") (class "Default")
      (node (ref "C10") (pin "2") (pinfunction "2_2") (pintype "passive"))
      (node (ref "R5") (pin "1") (pinfunction "1_1") (pintype "passive"))
      (node (ref "SW1") (pin "1") (pinfunction "1_1") (pintype "passive"))
      (node (ref "U2") (pin "7") (pinfunction "NRST_7") (pintype "passive"))
    )
    (net (code "26") (name "/NRST_CTRL") (class "Default")
      (node (ref "IC2") (pin "2") (pinfunction "K_2") (pintype "passive"))
      (node (ref "U2") (pin "33") (pinfunction "PB12_33") (pintype "passive"))
    )
    (net (code "27") (name "/OSCM") (class "Default")
      (node (ref "C11") (pin "1") (pinfunction "1_1") (pintype "passive"))
      (node (ref "R15") (pin "1") (pinfunction "1_1") (pintype "passive"))
      (node (ref "R19") (pin "1") (pinfunction "1_1") (pintype "passive"))
      (node (ref "U3") (pin "43") (pinfunction "OSCM_43") (pintype "passive"))
    )
    (net (code "28") (name "/OSC_IN") (class "Default")
      (node (ref "C12") (pin "2") (pinfunction "2_2") (pintype "passive"))
      (node (ref "U2") (pin "5") (pinfunction "PD0-OSC_IN_5") (pintype "passive"))
      (node (ref "X1") (pin "1") (pinfunction "1_1") (pintype "passive"))
    )
    (net (code "29") (name "/OSC_OUT") (class "Default")
      (node (ref "C13") (pin "2") (pinfunction "2_2") (pintype "passive"))
      (node (ref "U2") (pin "6") (pinfunction "PD1-OSC_OUT_6") (pintype "passive"))
      (node (ref "X1") (pin "2") (pinfunction "2_2") (pintype "passive"))
    )
    (net (code "30") (name "/OUTA+") (class "Default")
      (node (ref "JP7") (pin "1") (pinfunction "1_1") (pintype "passive"))
      (node (ref "U3") (pin "10") (pinfunction "OUTA+_10") (pintype "passive"))
      (node (ref "U3") (pin "11") (pinfunction "OUTA+_11") (pintype "passive"))
    )
    (net (code "31") (name "/OUTA-") (class "Default")
      (node (ref "JP7") (pin "2") (pinfunction "2_2") (pintype "passive"))
      (node (ref "U3") (pin "16") (pinfunction "OUTA-_16") (pintype "passive"))
      (node (ref "U3") (pin "17") (pinfunction "OUTA-_17") (pintype "passive"))
    )
    (net (code "32") (name "/OUTB+") (class "Default")
      (node (ref "JP7") (pin "3") (pinfunction "3_3") (pintype "passive"))
      (node (ref "U3") (pin "26") (pinfunction "OUTB+_26") (pintype "passive"))
      (node (ref "U3") (pin "27") (pinfunction "OUTB+_27") (pintype "passive"))
    )
    (net (code "33") (name "/OUTB-") (class "Default")
      (node (ref "JP7") (pin "4") (pinfunction "4_4") (pintype "passive"))
      (node (ref "U3") (pin "20") (pinfunction "OUTB-_20") (pintype "passive"))
      (node (ref "U3") (pin "21") (pinfunction "OUTB-_21") (pintype "passive"))
    )
    (net (code "34") (name "/PWM_OSCM") (class "Default")
      (node (ref "R19") (pin "2") (pinfunction "2_2") (pintype "passive"))
      (node (ref "U2") (pin "15") (pinfunction "PA1_15") (pintype "passive"))
    )
    (net (code "35") (name "/PWM_VREF") (class "Default")
      (node (ref "R24") (pin "2") (pinfunction "2_2") (pintype "passive"))
      (node (ref "U2") (pin "22") (pinfunction "PA6_22") (pintype "passive"))
    )
    (net (code "36") (name "/RESET") (class "Default")
      (node (ref "IC2") (pin "4") (pinfunction "C_4") (pintype "passive"))
      (node (ref "R20") (pin "1") (pinfunction "1_1") (pintype "passive"))
      (node (ref "U3") (pin "4") (pinfunction "RESET_4") (pintype "passive"))
    )
    (net (code "37") (name "/RSA") (class "Default")
      (node (ref "R6") (pin "1") (pinfunction "1_1") (pintype "passive"))
      (node (ref "U3") (pin "7") (pinfunction "RSA_7") (pintype "passive"))
      (node (ref "U3") (pin "8") (pinfunction "RSA_8") (pintype "passive"))
    )
    (net (code "38") (name "/RSB") (class "Default")
      (node (ref "R10") (pin "1") (pinfunction "1_1") (pintype "passive"))
      (node (ref "U3") (pin "29") (pinfunction "RSB_29") (pintype "passive"))
      (node (ref "U3") (pin "30") (pinfunction "RSB_30") (pintype "passive"))
    )
    (net (code "39") (name "/START_SW") (class "Default")
      (node (ref "C17") (pin "1") (pinfunction "1_1") (pintype "passive"))
      (node (ref "Q4") (pin "3") (pinfunction "C_3") (pintype "passive"))
      (node (ref "R37") (pin "2") (pinfunction "2_2") (pintype "passive"))
      (node (ref "U2") (pin "24") (pinfunction "PC4_24") (pintype "passive"))
    )
    (net (code "40") (name "/SWCLK") (class "Default")
      (node (ref "B8") (pin "2") (pinfunction "K_2") (pintype "passive"))
      (node (ref "JP2") (pin "1") (pinfunction "1_1") (pintype "passive"))
      (node (ref "U2") (pin "49") (pinfunction "PA14_49") (pintype "passive"))
    )
    (net (code "41") (name "/SWDIO") (class "Default")
      (node (ref "B7") (pin "2") (pinfunction "K_2") (pintype "passive"))
      (node (ref "JP2") (pin "2") (pinfunction "2_2") (pintype "passive"))
      (node (ref "U2") (pin "46") (pinfunction "PA13_46") (pintype "passive"))
    )
    (net (code "42") (name "/TB67S109_PWR_CTRL") (class "Default")
      (node (ref "R11") (pin "2") (pinfunction "2_2") (pintype "passive"))
      (node (ref "U2") (pin "36") (pinfunction "PB15_36") (pintype "passive"))
    )
    (net (code "43") (name "/UART4_RX") (class "Default")
      (node (ref "R33") (pin "1") (pinfunction "1_1") (pintype "passive"))
      (node (ref "U2") (pin "52") (pinfunction "PC11_52") (pintype "passive"))
    )
    (net (code "44") (name "/UART4_TX") (class "Default")
      (node (ref "R31") (pin "1") (pinfunction "1_1") (pintype "passive"))
      (node (ref "U2") (pin "51") (pinfunction "PC10_51") (pintype "passive"))
    )
    (net (code "45") (name "/VREF") (class "Default")
      (node (ref "C14") (pin "1") (pinfunction "1_1") (pintype "passive"))
      (node (ref "C16") (pin "1") (pinfunction "1_1") (pintype "passive"))
      (node (ref "R24") (pin "1") (pinfunction "1_1") (pintype "passive"))
      (node (ref "R41") (pin "2") (pinfunction "2_2") (pintype "passive"))
      (node (ref "R44") (pin "1") (pinfunction "1_1") (pintype "passive"))
      (node (ref "R47") (pin "1") (pinfunction "1_1") (pintype "passive"))
      (node (ref "RP1") (pin "1") (pinfunction "1_1") (pintype "passive"))
      (node (ref "RP1") (pin "2") (pinfunction "2_2") (pintype "passive"))
      (node (ref "U3") (pin "41") (pinfunction "VREFB_41") (pintype "passive"))
      (node (ref "U3") (pin "42") (pinfunction "VREFA_42") (pintype "passive"))
    )
    (net (code "46") (name "DGND") (class "Default")
      (node (ref "B1") (pin "1") (pinfunction "A_1") (pintype "passive"))
      (node (ref "B10") (pin "1") (pinfunction "A_1") (pintype "passive"))
      (node (ref "B10") (pin "2") (pinfunction "K_2") (pintype "passive"))
      (node (ref "B11") (pin "1") (pinfunction "A_1") (pintype "passive"))
      (node (ref "B12") (pin "1") (pinfunction "A_1") (pintype "passive"))
      (node (ref "B2") (pin "1") (pinfunction "A_1") (pintype "passive"))
      (node (ref "B2") (pin "2") (pinfunction "K_2") (pintype "passive"))
      (node (ref "B3") (pin "1") (pinfunction "A_1") (pintype "passive"))
      (node (ref "B4") (pin "1") (pinfunction "A_1") (pintype "passive"))
      (node (ref "B5") (pin "1") (pinfunction "A_1") (pintype "passive"))
      (node (ref "B6") (pin "1") (pinfunction "A_1") (pintype "passive"))
      (node (ref "B6") (pin "2") (pinfunction "K_2") (pintype "passive"))
      (node (ref "B7") (pin "1") (pinfunction "A_1") (pintype "passive"))
      (node (ref "B8") (pin "1") (pinfunction "A_1") (pintype "passive"))
      (node (ref "B9") (pin "1") (pinfunction "A_1") (pintype "passive"))
      (node (ref "C10") (pin "1") (pinfunction "1_1") (pintype "passive"))
      (node (ref "C12") (pin "1") (pinfunction "1_1") (pintype "passive"))
      (node (ref "C13") (pin "1") (pinfunction "1_1") (pintype "passive"))
      (node (ref "C17") (pin "2") (pinfunction "2_2") (pintype "passive"))
      (node (ref "C18") (pin "2") (pinfunction "2_2") (pintype "passive"))
      (node (ref "C19") (pin "1") (pinfunction "1_1") (pintype "passive"))
      (node (ref "C20") (pin "1") (pinfunction "1_1") (pintype "passive"))
      (node (ref "C21") (pin "1") (pinfunction "1_1") (pintype "passive"))
      (node (ref "C22") (pin "1") (pinfunction "1_1") (pintype "passive"))
      (node (ref "JP2") (pin "3") (pinfunction "3_3") (pintype "passive"))
      (node (ref "JP3") (pin "3") (pinfunction "3_3") (pintype "passive"))
      (node (ref "JP4") (pin "3") (pinfunction "3_3") (pintype "passive"))
      (node (ref "Q4") (pin "2") (pinfunction "E_2") (pintype "passive"))
      (node (ref "Q5") (pin "2") (pinfunction "E_2") (pintype "passive"))
      (node (ref "Q6") (pin "2") (pinfunction "E_2") (pintype "passive"))
      (node (ref "Q7") (pin "2") (pinfunction "E_2") (pintype "passive"))
      (node (ref "R22") (pin "1") (pinfunction "1_1") (pintype "passive"))
      (node (ref "R23") (pin "1") (pinfunction "1_1") (pintype "passive"))
      (node (ref "R48") (pin "1") (pinfunction "1_1") (pintype "passive"))
      (node (ref "R49") (pin "1") (pinfunction "1_1") (pintype "passive"))
      (node (ref "R53") (pin "1") (pinfunction "1_1") (pintype "passive"))
      (node (ref "SW1") (pin "2") (pinfunction "2_2") (pintype "passive"))
      (node (ref "U2") (pin "13") (pinfunction "VDDA_13") (pintype "passive"))
      (node (ref "U2") (pin "2") (pinfunction "PC13_2") (pintype "passive"))
      (node (ref "U2") (pin "32") (pinfunction "VDD_1_32") (pintype "passive"))
      (node (ref "U2") (pin "47") (pinfunction "VSS_2_47") (pintype "passive"))
      (node (ref "U2") (pin "63") (pinfunction "VSS_3_63") (pintype "passive"))
    )
    (net (code "47") (name "GND") (class "Default")
      (node (ref "C11") (pin "2") (pinfunction "2_2") (pintype "passive"))
      (node (ref "C14") (pin "2") (pinfunction "2_2") (pintype "passive"))
      (node (ref "C15") (pin "2") (pinfunction "2_2") (pintype "passive"))
      (node (ref "C2") (pin "2") (pinfunction "2_2") (pintype "passive"))
      (node (ref "C23") (pin "1") (pinfunction "1_1") (pintype "passive"))
      (node (ref "C24") (pin "1") (pinfunction "1_1") (pintype "passive"))
      (node (ref "C25") (pin "1") (pinfunction "1_1") (pintype "passive"))
      (node (ref "C26") (pin "1") (pinfunction "1_1") (pintype "passive"))
      (node (ref "C3") (pin "2") (pinfunction "2_2") (pintype "passive"))
      (node (ref "C4") (pin "2") (pinfunction "2_2") (pintype "passive"))
      (node (ref "C5") (pin "2") (pinfunction "2_2") (pintype "passive"))
      (node (ref "C6") (pin "2") (pinfunction "2_2") (pintype "passive"))
      (node (ref "C7") (pin "2") (pinfunction "2_2") (pintype "passive"))
      (node (ref "C8") (pin "2") (pinfunction "2_2") (pintype "passive"))
      (node (ref "C9") (pin "2") (pinfunction "2_2") (pintype "passive"))
      (node (ref "CON1") (pin "2") (pintype "power_in"))
      (node (ref "CON1") (pin "3") (pintype "power_in"))
      (node (ref "D1") (pin "1") (pinfunction "A_1") (pintype "passive"))
      (node (ref "E1") (pin "2") (pinfunction "K_2") (pintype "passive"))
      (node (ref "E2") (pin "2") (pinfunction "K_2") (pintype "passive"))
      (node (ref "IC1") (pin "3") (pinfunction "E_3") (pintype "passive"))
      (node (ref "IC2") (pin "3") (pinfunction "E_3") (pintype "passive"))
      (node (ref "IC3") (pin "3") (pinfunction "E_3") (pintype "passive"))
      (node (ref "IC4") (pin "3") (pinfunction "E_3") (pintype "passive"))
      (node (ref "IC5") (pin "3") (pinfunction "E_3") (pintype "passive"))
      (node (ref "IC6") (pin "4") (pinfunction "GND_4") (pintype "passive"))
      (node (ref "JP1") (pin "1") (pinfunction "1_1") (pintype "passive"))
      (node (ref "JP5") (pin "1") (pinfunction "1_1") (pintype "passive"))
      (node (ref "JP6") (pin "1") (pinfunction "1_1") (pintype "passive"))
      (node (ref "Q1") (pin "1") (pinfunction "G_1") (pintype "passive"))
      (node (ref "Q3") (pin "2") (pinfunction "E_2") (pintype "passive"))
      (node (ref "R14") (pin "2") (pinfunction "2_2") (pintype "passive"))
      (node (ref "R2") (pin "1") (pinfunction "1_1") (pintype "passive"))
      (node (ref "R3") (pin "1") (pinfunction "1_1") (pintype "passive"))
      (node (ref "R47") (pin "2") (pinfunction "2_2") (pintype "passive"))
      (node (ref "R53") (pin "2") (pinfunction "2_2") (pintype "passive"))
      (node (ref "R54") (pin "1") (pinfunction "1_1") (pintype "passive"))
      (node (ref "R55") (pin "1") (pinfunction "1_1") (pintype "passive"))
      (node (ref "R56") (pin "1") (pinfunction "1_1") (pintype "passive"))
      (node (ref "R57") (pin "1") (pinfunction "1_1") (pintype "passive"))
      (node (ref "RP1") (pin "3") (pinfunction "3_3") (pintype "passive"))
      (node (ref "U1") (pin "1") (pinfunction "GND_1") (pintype "passive"))
      (node (ref "U3") (pin "15") (pinfunction "GND_15") (pintype "passive"))
      (node (ref "U3") (pin "18") (pinfunction "GND_18") (pintype "passive"))
      (node (ref "U3") (pin "19") (pinfunction "GND_19") (pintype "passive"))
      (node (ref "U3") (pin "22") (pinfunction "GND_22") (pintype "passive"))
      (node (ref "U3") (pin "40") (pinfunction "GND_40") (pintype "passive"))
      (node (ref "U3") (pin "49") (pinfunction "EP_49") (pintype "passive"))
      (node (ref "U3") (pin "5") (pinfunction "GND_5") (pintype "passive"))
      (node (ref "U4") (pin "1") (pinfunction "1~{A}_1") (pintype "passive"))
      (node (ref "U4") (pin "14") (pinfunction "1CEXT_14") (pintype "passive"))
      (node (ref "V1") (pin "1") (pinfunction "GND_1") (pintype "passive"))
      (node (ref "V2") (pin "1") (pinfunction "GND_1") (pintype "passive"))
    )
    (net (code "48") (name "Net-(B3-K)") (class "Default")
      (node (ref "B3") (pin "2") (pinfunction "K_2") (pintype "passive"))
      (node (ref "JP3") (pin "2") (pinfunction "2_2") (pintype "passive"))
      (node (ref "R32") (pin "2") (pinfunction "2_2") (pintype "passive"))
    )
    (net (code "49") (name "Net-(B4-K)") (class "Default")
      (node (ref "B4") (pin "2") (pinfunction "K_2") (pintype "passive"))
      (node (ref "JP3") (pin "1") (pinfunction "1_1") (pintype "passive"))
      (node (ref "R30") (pin "2") (pinfunction "2_2") (pintype "passive"))
    )
    (net (code "50") (name "Net-(B11-K)") (class "Default")
      (node (ref "B11") (pin "2") (pinfunction "K_2") (pintype "passive"))
      (node (ref "JP4") (pin "2") (pinfunction "2_2") (pintype "passive"))
      (node (ref "R33") (pin "2") (pinfunction "2_2") (pintype "passive"))
    )
    (net (code "51") (name "Net-(B12-K)") (class "Default")
      (node (ref "B12") (pin "2") (pinfunction "K_2") (pintype "passive"))
      (node (ref "JP4") (pin "1") (pinfunction "1_1") (pintype "passive"))
      (node (ref "R31") (pin "2") (pinfunction "2_2") (pintype "passive"))
    )
    (net (code "52") (name "Net-(C23-Pad2)") (class "Default")
      (node (ref "C23") (pin "2") (pinfunction "2_2") (pintype "passive"))
      (node (ref "R54") (pin "2") (pinfunction "2_2") (pintype "passive"))
      (node (ref "SP1") (pin "1") (pinfunction "1_1") (pintype "passive"))
    )
    (net (code "53") (name "Net-(C24-Pad2)") (class "Default")
      (node (ref "C24") (pin "2") (pinfunction "2_2") (pintype "passive"))
      (node (ref "R55") (pin "2") (pinfunction "2_2") (pintype "passive"))
      (node (ref "SP3") (pin "1") (pinfunction "1_1") (pintype "passive"))
    )
    (net (code "54") (name "Net-(C25-Pad2)") (class "Default")
      (node (ref "C25") (pin "2") (pinfunction "2_2") (pintype "passive"))
      (node (ref "R56") (pin "2") (pinfunction "2_2") (pintype "passive"))
      (node (ref "SP2") (pin "1") (pinfunction "1_1") (pintype "passive"))
    )
    (net (code "55") (name "Net-(C26-Pad2)") (class "Default")
      (node (ref "C26") (pin "2") (pinfunction "2_2") (pintype "passive"))
      (node (ref "R57") (pin "2") (pinfunction "2_2") (pintype "passive"))
      (node (ref "SP4") (pin "1") (pinfunction "1_1") (pintype "passive"))
    )
    (net (code "56") (name "Net-(D1-K)") (class "Default")
      (node (ref "D1") (pin "2") (pinfunction "K_2") (pintype "passive"))
      (node (ref "L1") (pin "1") (pinfunction "1_1") (pintype "passive"))
      (node (ref "U1") (pin "3") (pinfunction "SW_3") (pintype "passive"))
    )
    (net (code "57") (name "Net-(IC1-A)") (class "Default")
      (node (ref "IC1") (pin "1") (pinfunction "A_1") (pintype "passive"))
      (node (ref "R18") (pin "2") (pinfunction "2_2") (pintype "passive"))
    )
    (net (code "58") (name "Net-(IC2-A)") (class "Default")
      (node (ref "IC2") (pin "1") (pinfunction "A_1") (pintype "passive"))
      (node (ref "R21") (pin "2") (pinfunction "2_2") (pintype "passive"))
    )
    (net (code "59") (name "Net-(IC3-A)") (class "Default")
      (node (ref "IC3") (pin "1") (pinfunction "A_1") (pintype "passive"))
      (node (ref "R27") (pin "2") (pinfunction "2_2") (pintype "passive"))
    )
    (net (code "60") (name "Net-(IC4-A)") (class "Default")
      (node (ref "IC4") (pin "1") (pinfunction "A_1") (pintype "passive"))
      (node (ref "R29") (pin "2") (pinfunction "2_2") (pintype "passive"))
    )
    (net (code "61") (name "Net-(IC5-A)") (class "Default")
      (node (ref "IC5") (pin "1") (pinfunction "A_1") (pintype "passive"))
      (node (ref "R36") (pin "2") (pinfunction "2_2") (pintype "passive"))
    )
    (net (code "62") (name "Net-(IC6-AN)") (class "Default")
      (node (ref "IC6") (pin "1") (pinfunction "AN_1") (pintype "passive"))
      (node (ref "R52") (pin "2") (pinfunction "2_2") (pintype "passive"))
    )
    (net (code "63") (name "Net-(IC6-VCC)") (class "Default")
      (node (ref "IC6") (pin "6") (pinfunction "VCC_6") (pintype "passive"))
      (node (ref "R50") (pin "2") (pinfunction "2_2") (pintype "passive"))
    )
    (net (code "64") (name "Net-(JP5-Pad2)") (class "Default")
      (node (ref "JP5") (pin "2") (pinfunction "2_2") (pintype "passive"))
      (node (ref "R42") (pin "1") (pinfunction "1_1") (pintype "passive"))
      (node (ref "R45") (pin "2") (pinfunction "2_2") (pintype "passive"))
    )
    (net (code "65") (name "Net-(JP6-Pad2)") (class "Default")
      (node (ref "JP6") (pin "2") (pinfunction "2_2") (pintype "passive"))
      (node (ref "R43") (pin "1") (pinfunction "1_1") (pintype "passive"))
      (node (ref "R46") (pin "2") (pinfunction "2_2") (pintype "passive"))
    )
    (net (code "66") (name "Net-(LED1-K)") (class "Default")
      (node (ref "LED1") (pin "2") (pinfunction "K_2") (pintype "passive"))
      (node (ref "R2") (pin "2") (pinfunction "2_2") (pintype "passive"))
    )
    (net (code "67") (name "Net-(LED2-K)") (class "Default")
      (node (ref "LED2") (pin "2") (pinfunction "K_2") (pintype "passive"))
      (node (ref "R12") (pin "2") (pinfunction "2_2") (pintype "passive"))
    )
    (net (code "68") (name "Net-(LED3-K)") (class "Default")
      (node (ref "LED3") (pin "2") (pinfunction "K_2") (pintype "passive"))
      (node (ref "R13") (pin "2") (pinfunction "2_2") (pintype "passive"))
    )
    (net (code "69") (name "Net-(Q1-D)") (class "Default")
      (node (ref "Q1") (pin "2") (pinfunction "D_2") (pintype "passive"))
      (node (ref "S1") (pin "1") (pinfunction "1_1") (pintype "passive"))
    )
    (net (code "70") (name "Net-(Q2-G)") (class "Default")
      (node (ref "Q2") (pin "1") (pinfunction "G_1") (pintype "passive"))
      (node (ref "Q3") (pin "3") (pinfunction "C_3") (pintype "passive"))
      (node (ref "R4") (pin "1") (pinfunction "1_1") (pintype "passive"))
    )
    (net (code "71") (name "Net-(Q3-B)") (class "Default")
      (node (ref "Q3") (pin "1") (pinfunction "B_1") (pintype "passive"))
      (node (ref "R11") (pin "1") (pinfunction "1_1") (pintype "passive"))
      (node (ref "R14") (pin "1") (pinfunction "1_1") (pintype "passive"))
    )
    (net (code "72") (name "Net-(Q4-B)") (class "Default")
      (node (ref "Q4") (pin "1") (pinfunction "B_1") (pintype "passive"))
      (node (ref "Q6") (pin "3") (pinfunction "C_3") (pintype "passive"))
      (node (ref "R39") (pin "2") (pinfunction "2_2") (pintype "passive"))
    )
    (net (code "73") (name "Net-(Q5-B)") (class "Default")
      (node (ref "Q5") (pin "1") (pinfunction "B_1") (pintype "passive"))
      (node (ref "Q7") (pin "3") (pinfunction "C_3") (pintype "passive"))
      (node (ref "R40") (pin "2") (pinfunction "2_2") (pintype "passive"))
    )
    (net (code "74") (name "Net-(Q6-B)") (class "Default")
      (node (ref "Q6") (pin "1") (pinfunction "B_1") (pintype "passive"))
      (node (ref "R45") (pin "1") (pinfunction "1_1") (pintype "passive"))
      (node (ref "R48") (pin "2") (pinfunction "2_2") (pintype "passive"))
    )
    (net (code "75") (name "Net-(Q7-B)") (class "Default")
      (node (ref "Q7") (pin "1") (pinfunction "B_1") (pintype "passive"))
      (node (ref "R46") (pin "1") (pinfunction "1_1") (pintype "passive"))
      (node (ref "R49") (pin "2") (pinfunction "2_2") (pintype "passive"))
    )
    (net (code "76") (name "Net-(U1-FB)") (class "Default")
      (node (ref "R1") (pin "1") (pinfunction "1_1") (pintype "passive"))
      (node (ref "R3") (pin "2") (pinfunction "2_2") (pintype "passive"))
      (node (ref "U1") (pin "2") (pinfunction "FB_2") (pintype "passive"))
    )
    (net (code "77") (name "Net-(U1-VC)") (class "Default")
      (node (ref "C1") (pin "2") (pinfunction "2_2") (pintype "passive"))
      (node (ref "U1") (pin "4") (pinfunction "VC_4") (pintype "passive"))
    )
    (net (code "78") (name "Net-(U4-1Q)") (class "Default")
      (node (ref "R44") (pin "2") (pinfunction "2_2") (pintype "passive"))
      (node (ref "U4") (pin "13") (pinfunction "1Q_13") (pintype "passive"))
    )
    (net (code "79") (name "Net-(U4-1REXT{slash}CEXT)") (class "Default")
      (node (ref "C15") (pin "1") (pinfunction "1_1") (pintype "passive"))
      (node (ref "R34") (pin "1") (pinfunction "1_1") (pintype "passive"))
      (node (ref "U4") (pin "15") (pinfunction "1REXT/CEXT_15") (pintype "passive"))
    )
    (net (code "80") (name "POWER_IN") (class "Default")
      (node (ref "CON1") (pin "1") (pintype "power_in"))
      (node (ref "JP1") (pin "2") (pinfunction "2_2") (pintype "passive"))
      (node (ref "S1") (pin "2") (pinfunction "2_2") (pintype "passive"))
    )
    (net (code "81") (name "TB67S109_5V") (class "Default")
      (node (ref "C16") (pin "2") (pinfunction "2_2") (pintype "passive"))
      (node (ref "Q2") (pin "3") (pinfunction "D_3") (pintype "passive"))
      (node (ref "R15") (pin "2") (pinfunction "2_2") (pintype "passive"))
      (node (ref "R34") (pin "2") (pinfunction "2_2") (pintype "passive"))
      (node (ref "R41") (pin "1") (pinfunction "1_1") (pintype "passive"))
      (node (ref "U3") (pin "34") (pinfunction "VCC_34") (pintype "passive"))
      (node (ref "U4") (pin "16") (pinfunction "VDD_16") (pintype "passive"))
      (node (ref "U4") (pin "3") (pinfunction "1~{RD}_3") (pintype "passive"))
    )
    (net (code "82") (name "unconnected-(S1-Pad3)") (class "Default")
      (node (ref "S1") (pin "3") (pinfunction "3_3") (pintype "passive"))
    )
    (net (code "83") (name "unconnected-(U2-PA0-WKUP-Pad14)") (class "Default")
      (node (ref "U2") (pin "14") (pinfunction "PA0-WKUP_14") (pintype "passive"))
    )
    (net (code "84") (name "unconnected-(U2-PA2-Pad16)") (class "Default")
      (node (ref "U2") (pin "16") (pinfunction "PA2_16") (pintype "passive"))
    )
    (net (code "85") (name "unconnected-(U2-PA3-Pad17)") (class "Default")
      (node (ref "U2") (pin "17") (pinfunction "PA3_17") (pintype "passive"))
    )
    (net (code "86") (name "unconnected-(U2-PA4-Pad20)") (class "Default")
      (node (ref "U2") (pin "20") (pinfunction "PA4_20") (pintype "passive"))
    )
    (net (code "87") (name "unconnected-(U2-PA5-Pad21)") (class "Default")
      (node (ref "U2") (pin "21") (pinfunction "PA5_21") (pintype "passive"))
    )
    (net (code "88") (name "unconnected-(U2-PA7-Pad23)") (class "Default")
      (node (ref "U2") (pin "23") (pinfunction "PA7_23") (pintype "passive"))
    )
    (net (code "89") (name "unconnected-(U2-PA11-Pad44)") (class "Default")
      (node (ref "U2") (pin "44") (pinfunction "PA11_44") (pintype "passive"))
    )
    (net (code "90") (name "unconnected-(U2-PA12-Pad45)") (class "Default")
      (node (ref "U2") (pin "45") (pinfunction "PA12_45") (pintype "passive"))
    )
    (net (code "91") (name "unconnected-(U2-PA15-Pad50)") (class "Default")
      (node (ref "U2") (pin "50") (pinfunction "PA15_50") (pintype "passive"))
    )
    (net (code "92") (name "unconnected-(U2-PB0-Pad26)") (class "Default")
      (node (ref "U2") (pin "26") (pinfunction "PB0_26") (pintype "passive"))
    )
    (net (code "93") (name "unconnected-(U2-PB1-Pad27)") (class "Default")
      (node (ref "U2") (pin "27") (pinfunction "PB1_27") (pintype "passive"))
    )
    (net (code "94") (name "unconnected-(U2-PB5-Pad57)") (class "Default")
      (node (ref "U2") (pin "57") (pinfunction "PB5_57") (pintype "passive"))
    )
    (net (code "95") (name "unconnected-(U2-PB7-Pad59)") (class "Default")
      (node (ref "U2") (pin "59") (pinfunction "PB7_59") (pintype "passive"))
    )
    (net (code "96") (name "unconnected-(U2-PB8-Pad61)") (class "Default")
      (node (ref "U2") (pin "61") (pinfunction "PB8_61") (pintype "passive"))
    )
    (net (code "97") (name "unconnected-(U2-PB9-Pad62)") (class "Default")
      (node (ref "U2") (pin "62") (pinfunction "PB9_62") (pintype "passive"))
    )
    (net (code "98") (name "unconnected-(U2-PB10-Pad29)") (class "Default")
      (node (ref "U2") (pin "29") (pinfunction "PB10_29") (pintype "passive"))
    )
    (net (code "99") (name "unconnected-(U2-PB11-Pad30)") (class "Default")
      (node (ref "U2") (pin "30") (pinfunction "PB11_30") (pintype "passive"))
    )
    (net (code "100") (name "unconnected-(U2-PC0-Pad8)") (class "Default")
      (node (ref "U2") (pin "8") (pinfunction "PC0_8") (pintype "passive"))
    )
    (net (code "101") (name "unconnected-(U2-PC1-Pad9)") (class "Default")
      (node (ref "U2") (pin "9") (pinfunction "PC1_9") (pintype "passive"))
    )
    (net (code "102") (name "unconnected-(U2-PC2-Pad10)") (class "Default")
      (node (ref "U2") (pin "10") (pinfunction "PC2_10") (pintype "passive"))
    )
    (net (code "103") (name "unconnected-(U2-PC3-Pad11)") (class "Default")
      (node (ref "U2") (pin "11") (pinfunction "PC3_11") (pintype "passive"))
    )
    (net (code "104") (name "unconnected-(U2-PC7-Pad38)") (class "Default")
      (node (ref "U2") (pin "38") (pinfunction "PC7_38") (pintype "passive"))
    )
    (net (code "105") (name "unconnected-(U2-PC8-Pad39)") (class "Default")
      (node (ref "U2") (pin "39") (pinfunction "PC8_39") (pintype "passive"))
    )
    (net (code "106") (name "unconnected-(U2-PC9-Pad40)") (class "Default")
      (node (ref "U2") (pin "40") (pinfunction "PC9_40") (pintype "passive"))
    )
    (net (code "107") (name "unconnected-(U2-PC12-Pad53)") (class "Default")
      (node (ref "U2") (pin "53") (pinfunction "PC12_53") (pintype "passive"))
    )
    (net (code "108") (name "unconnected-(U2-PC14-OSC32_IN-Pad3)") (class "Default")
      (node (ref "U2") (pin "3") (pinfunction "PC14-OSC32_IN_3") (pintype "passive"))
    )
    (net (code "109") (name "unconnected-(U2-PC15-OSC32_OUT-Pad4)") (class "Default")
      (node (ref "U2") (pin "4") (pinfunction "PC15-OSC32_OUT_4") (pintype "passive"))
    )
    (net (code "110") (name "unconnected-(U2-PD2-Pad54)") (class "Default")
      (node (ref "U2") (pin "54") (pinfunction "PD2_54") (pintype "passive"))
    )
    (net (code "111") (name "unconnected-(U2-VDD_4-Pad19)") (class "Default")
      (node (ref "U2") (pin "19") (pinfunction "VDD_4_19") (pintype "passive"))
    )
    (net (code "112") (name "unconnected-(U2-VSS_4-Pad18)") (class "Default")
      (node (ref "U2") (pin "18") (pinfunction "VSS_4_18") (pintype "passive"))
    )
    (net (code "113") (name "unconnected-(U3-NC-Pad1)") (class "Default")
      (node (ref "U3") (pin "1") (pinfunction "NC_1") (pintype "passive"))
    )
    (net (code "114") (name "unconnected-(U3-NC-Pad6)") (class "Default")
      (node (ref "U3") (pin "6") (pinfunction "NC_6") (pintype "passive"))
    )
    (net (code "115") (name "unconnected-(U3-NC-Pad9)") (class "Default")
      (node (ref "U3") (pin "9") (pinfunction "NC_9") (pintype "passive"))
    )
    (net (code "116") (name "unconnected-(U3-NC-Pad12)") (class "Default")
      (node (ref "U3") (pin "12") (pinfunction "NC_12") (pintype "passive"))
    )
    (net (code "117") (name "unconnected-(U3-NC-Pad13)") (class "Default")
      (node (ref "U3") (pin "13") (pinfunction "NC_13") (pintype "passive"))
    )
    (net (code "118") (name "unconnected-(U3-NC-Pad14)") (class "Default")
      (node (ref "U3") (pin "14") (pinfunction "NC_14") (pintype "passive"))
    )
    (net (code "119") (name "unconnected-(U3-NC-Pad23)") (class "Default")
      (node (ref "U3") (pin "23") (pinfunction "NC_23") (pintype "passive"))
    )
    (net (code "120") (name "unconnected-(U3-NC-Pad24)") (class "Default")
      (node (ref "U3") (pin "24") (pinfunction "NC_24") (pintype "passive"))
    )
    (net (code "121") (name "unconnected-(U3-NC-Pad25)") (class "Default")
      (node (ref "U3") (pin "25") (pinfunction "NC_25") (pintype "passive"))
    )
    (net (code "122") (name "unconnected-(U3-NC-Pad28)") (class "Default")
      (node (ref "U3") (pin "28") (pinfunction "NC_28") (pintype "passive"))
    )
    (net (code "123") (name "unconnected-(U3-NC-Pad31)") (class "Default")
      (node (ref "U3") (pin "31") (pinfunction "NC_31") (pintype "passive"))
    )
    (net (code "124") (name "unconnected-(U3-NC-Pad33)") (class "Default")
      (node (ref "U3") (pin "33") (pinfunction "NC_33") (pintype "passive"))
    )
    (net (code "125") (name "unconnected-(U3-NC-Pad35)") (class "Default")
      (node (ref "U3") (pin "35") (pinfunction "NC_35") (pintype "passive"))
    )
    (net (code "126") (name "unconnected-(U3-NC-Pad36)") (class "Default")
      (node (ref "U3") (pin "36") (pinfunction "NC_36") (pintype "passive"))
    )
    (net (code "127") (name "unconnected-(U3-NC-Pad37)") (class "Default")
      (node (ref "U3") (pin "37") (pinfunction "NC_37") (pintype "passive"))
    )
    (net (code "128") (name "unconnected-(U3-NC-Pad48)") (class "Default")
      (node (ref "U3") (pin "48") (pinfunction "NC_48") (pintype "passive"))
    )
    (net (code "129") (name "unconnected-(U4-1~{Q}-Pad4)") (class "Default")
      (node (ref "U4") (pin "4") (pinfunction "1~{Q}_4") (pintype "passive"))
    )
    (net (code "130") (name "unconnected-(U4-2B-Pad10)") (class "Default")
      (node (ref "U4") (pin "10") (pinfunction "2B_10") (pintype "passive"))
    )
    (net (code "131") (name "unconnected-(U4-2CEXT-Pad6)") (class "Default")
      (node (ref "U4") (pin "6") (pinfunction "2CEXT_6") (pintype "passive"))
    )
    (net (code "132") (name "unconnected-(U4-2Q-Pad5)") (class "Default")
      (node (ref "U4") (pin "5") (pinfunction "2Q_5") (pintype "passive"))
    )
    (net (code "133") (name "unconnected-(U4-2REXT{slash}CEXT-Pad7)") (class "Default")
      (node (ref "U4") (pin "7") (pinfunction "2REXT/CEXT_7") (pintype "passive"))
    )
    (net (code "134") (name "unconnected-(U4-2~{A}-Pad9)") (class "Default")
      (node (ref "U4") (pin "9") (pinfunction "2~{A}_9") (pintype "passive"))
    )
    (net (code "135") (name "unconnected-(U4-2~{Q}-Pad12)") (class "Default")
      (node (ref "U4") (pin "12") (pinfunction "2~{Q}_12") (pintype "passive"))
    )
    (net (code "136") (name "unconnected-(U4-2~{RD}-Pad11)") (class "Default")
      (node (ref "U4") (pin "11") (pinfunction "2~{RD}_11") (pintype "passive"))
    )
    (net (code "137") (name "unconnected-(U4-GND-Pad8)") (class "Default")
      (node (ref "U4") (pin "8") (pinfunction "GND_8") (pintype "passive"))
    )
  )
)
